# Peltier_1s.net
KiCad netlist of a schematic drawn in Altium Designer
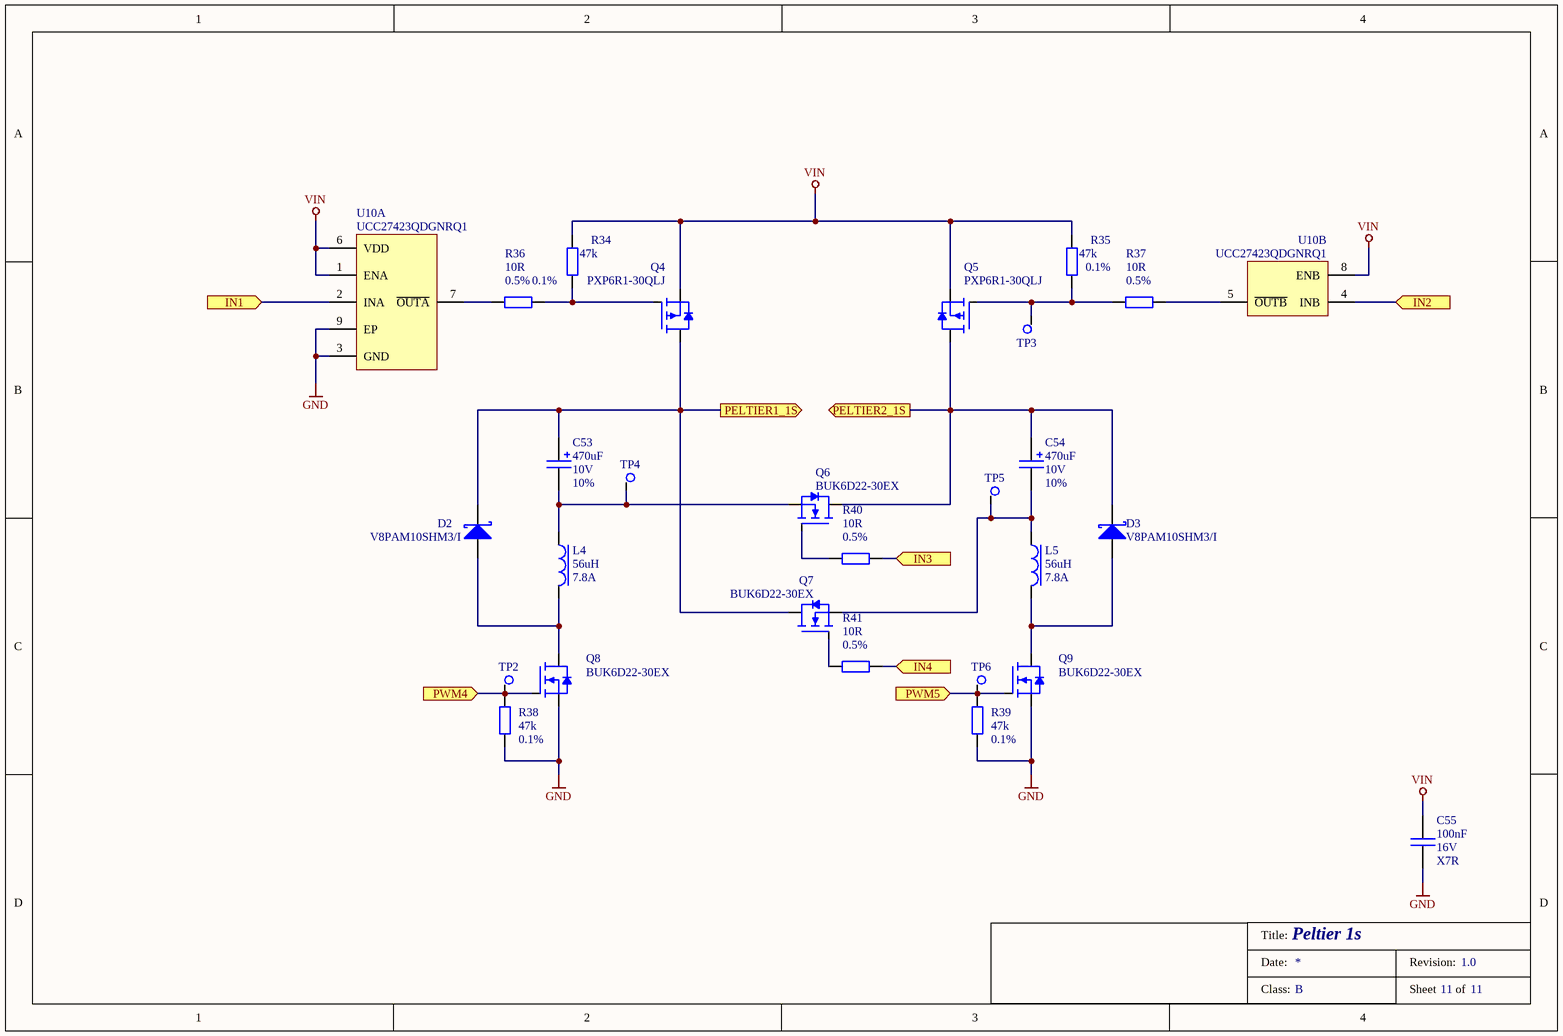
[diagram p0: Peltier_1s.SchDoc]

(export (version "E")
  (design (tool "Eeschema 10.0.6"))
  (components
    (comp (ref "C53")
      (value "470uF")
      (footprint "CT_X")
      (fields
        (field (name "TOLERANCE") "10%")
        (field (name "VOLTAGE") "10V")
        (field (name "PART NUMBER") "CT_470uF_10V_X")
        (field (name "MANUFACTURER") "Kemet")
        (field (name "MANUFACTURER PART NUMBER") "T491X477K010AT")
      )
      (libsource (lib "ProgresjaSpace") (part "C_Pol"))
    )
    (comp (ref "C54")
      (value "470uF")
      (footprint "CT_X")
      (fields
        (field (name "TOLERANCE") "10%")
        (field (name "VOLTAGE") "10V")
        (field (name "PART NUMBER") "CT_470uF_10V_X")
        (field (name "MANUFACTURER") "Kemet")
        (field (name "MANUFACTURER PART NUMBER") "T491X477K010AT")
      )
      (libsource (lib "ProgresjaSpace") (part "C_Pol"))
    )
    (comp (ref "C55")
      (value "100nF")
      (footprint "C_0402")
      (description "Capacitor")
      (fields
        (field (name "VOLTAGE") "16V")
        (field (name "DIELECTRIC") "X7R")
        (field (name "PART NUMBER") "C_100nF_16V_0402")
        (field (name "MANUFACTURER") "Kemet")
      )
      (libsource (lib "ProgresjaSpace") (part "C"))
    )
    (comp (ref "D2")
      (value "V8PAM10SHM3/I")
      (footprint "D_DO_221BC")
      (description "Surface-Mount TMBS (Trench MOS Barrier Schottky) Rectifier")
      (fields (field (name "MANUFACTURER") "Vishay") (field (name "Comment") "D_SHOTTKY"))
      (libsource (lib "ProgresjaSpace") (part "D_SHOTTKY"))
    )
    (comp (ref "D3")
      (value "V8PAM10SHM3/I")
      (footprint "D_DO_221BC")
      (description "Surface-Mount TMBS (Trench MOS Barrier Schottky) Rectifier")
      (fields (field (name "MANUFACTURER") "Vishay") (field (name "Comment") "D_SHOTTKY"))
      (libsource (lib "ProgresjaSpace") (part "D_SHOTTKY"))
    )
    (comp (ref "L4")
      (value "56uH")
      (footprint "L_SRP1770")
      (description "Shielded automotive Inductors, High Temperature")
      (fields
        (field (name "MAX CURRENT") "7.8A")
        (field (name "PART NUMBER") "SRP1770TA-560M")
        (field (name "MANUFACTURER") "Bourns")
      )
      (libsource (lib "ProgresjaSpace") (part "L_Core"))
    )
    (comp (ref "L5")
      (value "56uH")
      (footprint "L_SRP1770")
      (description "Shielded automotive Inductors, High Temperature")
      (fields
        (field (name "MAX CURRENT") "7.8A")
        (field (name "PART NUMBER") "SRP1770TA-560M")
        (field (name "MANUFACTURER") "Bourns")
      )
      (libsource (lib "ProgresjaSpace") (part "L_Core"))
    )
    (comp (ref "Q4")
      (value "PXP6R1-30QLJ")
      (footprint "WDFN_8")
      (description "Low Vgs Single P-Channel")
      (fields (field (name "MANUFACTURER") "NEXPERIA") (field (name "Comment") "Q_PMOSFET"))
      (libsource (lib "ProgresjaSpace") (part "Q_PMOSFET"))
    )
    (comp (ref "Q5")
      (value "PXP6R1-30QLJ")
      (footprint "WDFN_8")
      (description "Low Vgs Single P-Channel")
      (fields (field (name "MANUFACTURER") "NEXPERIA") (field (name "Comment") "Q_PMOSFET"))
      (libsource (lib "ProgresjaSpace") (part "Q_PMOSFET"))
    )
    (comp (ref "Q6")
      (value "BUK6D22-30EX")
      (footprint "SOT_1220")
      (description "Automotive N-Channel 30 V, Low Vgs Treshold")
      (fields (field (name "MANUFACTURER") "NEXPERIA") (field (name "Comment") "Q_NMOSFET"))
      (libsource (lib "ProgresjaSpace") (part "Q_NMOSFET"))
    )
    (comp (ref "Q7")
      (value "BUK6D22-30EX")
      (footprint "SOT_1220")
      (description "Automotive N-Channel 30 V, Low Vgs Treshold")
      (fields (field (name "MANUFACTURER") "NEXPERIA") (field (name "Comment") "Q_NMOSFET"))
      (libsource (lib "ProgresjaSpace") (part "Q_NMOSFET"))
    )
    (comp (ref "Q8")
      (value "BUK6D22-30EX")
      (footprint "SOT_1220")
      (description "Automotive N-Channel 30 V, Low Vgs Treshold")
      (fields (field (name "MANUFACTURER") "NEXPERIA") (field (name "Comment") "Q_NMOSFET"))
      (libsource (lib "ProgresjaSpace") (part "Q_NMOSFET"))
    )
    (comp (ref "Q9")
      (value "BUK6D22-30EX")
      (footprint "SOT_1220")
      (description "Automotive N-Channel 30 V, Low Vgs Treshold")
      (fields (field (name "MANUFACTURER") "NEXPERIA") (field (name "Comment") "Q_NMOSFET"))
      (libsource (lib "ProgresjaSpace") (part "Q_NMOSFET"))
    )
    (comp (ref "R34")
      (value "47k")
      (footprint "R_0402")
      (fields
        (field (name "TOLERANCE") "0.1%")
        (field (name "PART NUMBER") "R_47k_50V_0402")
        (field (name "VOLTAGE") "50V")
        (field (name "MANUFACTURER") "Vishay")
      )
      (libsource (lib "") (part "R_2"))
    )
    (comp (ref "R35")
      (value "47k")
      (footprint "R_0402")
      (fields
        (field (name "TOLERANCE") "0.1%")
        (field (name "PART NUMBER") "R_47k_50V_0402")
        (field (name "VOLTAGE") "50V")
        (field (name "MANUFACTURER") "Vishay")
      )
      (libsource (lib "") (part "R_2"))
    )
    (comp (ref "R36")
      (value "10R")
      (footprint "R_0603")
      (fields
        (field (name "TOLERANCE") "0.5%")
        (field (name "PART NUMBER") "R_10R_75V_0603")
        (field (name "VOLTAGE") "75V")
        (field (name "MANUFACTURER") "Vishay")
      )
      (libsource (lib "ProgresjaSpace") (part "R"))
    )
    (comp (ref "R37")
      (value "10R")
      (footprint "R_0603")
      (fields
        (field (name "TOLERANCE") "0.5%")
        (field (name "PART NUMBER") "R_10R_75V_0603")
        (field (name "VOLTAGE") "75V")
        (field (name "MANUFACTURER") "Vishay")
      )
      (libsource (lib "ProgresjaSpace") (part "R"))
    )
    (comp (ref "R38")
      (value "47k")
      (footprint "R_0402")
      (fields
        (field (name "TOLERANCE") "0.1%")
        (field (name "PART NUMBER") "R_47k_50V_0402")
        (field (name "VOLTAGE") "50V")
        (field (name "MANUFACTURER") "Vishay")
      )
      (libsource (lib "") (part "R_1"))
    )
    (comp (ref "R39")
      (value "47k")
      (footprint "R_0402")
      (fields
        (field (name "TOLERANCE") "0.1%")
        (field (name "PART NUMBER") "R_47k_50V_0402")
        (field (name "VOLTAGE") "50V")
        (field (name "MANUFACTURER") "Vishay")
      )
      (libsource (lib "") (part "R_1"))
    )
    (comp (ref "R40")
      (value "10R")
      (footprint "R_0603")
      (fields
        (field (name "TOLERANCE") "0.5%")
        (field (name "PART NUMBER") "R_10R_75V_0603")
        (field (name "VOLTAGE") "75V")
        (field (name "MANUFACTURER") "Vishay")
      )
      (libsource (lib "ProgresjaSpace") (part "R"))
    )
    (comp (ref "R41")
      (value "10R")
      (footprint "R_0603")
      (fields
        (field (name "TOLERANCE") "0.5%")
        (field (name "PART NUMBER") "R_10R_75V_0603")
        (field (name "VOLTAGE") "75V")
        (field (name "MANUFACTURER") "Vishay")
      )
      (libsource (lib "ProgresjaSpace") (part "R"))
    )
    (comp (ref "TP2")
      (value "TP_TestPoint")
      (footprint "TP_01")
      (fields (field (name "PART NUMBER") "TestPoint1") (field (name "MANUFACTURER") "Progresja Space"))
      (libsource (lib "ProgresjaSpace") (part "TP_TestPoint"))
    )
    (comp (ref "TP3")
      (value "TP_TestPoint")
      (footprint "TP_01")
      (fields (field (name "PART NUMBER") "TestPoint1") (field (name "MANUFACTURER") "Progresja Space"))
      (libsource (lib "ProgresjaSpace") (part "TP_TestPoint"))
    )
    (comp (ref "TP4")
      (value "TP_TestPoint")
      (footprint "TP_01")
      (fields (field (name "PART NUMBER") "TestPoint1") (field (name "MANUFACTURER") "Progresja Space"))
      (libsource (lib "ProgresjaSpace") (part "TP_TestPoint"))
    )
    (comp (ref "TP5")
      (value "TP_TestPoint")
      (footprint "TP_01")
      (fields (field (name "PART NUMBER") "TestPoint1") (field (name "MANUFACTURER") "Progresja Space"))
      (libsource (lib "ProgresjaSpace") (part "TP_TestPoint"))
    )
    (comp (ref "TP6")
      (value "TP_TestPoint")
      (footprint "TP_01")
      (fields (field (name "PART NUMBER") "TestPoint1") (field (name "MANUFACTURER") "Progresja Space"))
      (libsource (lib "ProgresjaSpace") (part "TP_TestPoint"))
    )
    (comp (ref "U10")
      (value "UCC27423QDGNRQ1")
      (footprint "MSOP_8")
      (description "Dual 4-A High-Speed Low-Side MOSFET Drivers With Enable")
      (fields (field (name "PART NUMBER") "UCC27423") (field (name "MANUFACTURER") "TI"))
      (libsource (lib "ProgresjaSpace") (part "IC_UCC27423_Q1"))
    )
  )
  (nets
    (net (code "1") (name "/IN1") (class "Default")
      (node (ref "U10") (pin "2") (pinfunction "INA_2") (pintype "passive"))
    )
    (net (code "2") (name "/IN2") (class "Default")
      (node (ref "U10") (pin "4") (pinfunction "INB_4") (pintype "passive"))
    )
    (net (code "3") (name "/IN3") (class "Default")
      (node (ref "R40") (pin "2") (pinfunction "2_2") (pintype "passive"))
    )
    (net (code "4") (name "/IN4") (class "Default")
      (node (ref "R41") (pin "2") (pinfunction "2_2") (pintype "passive"))
    )
    (net (code "5") (name "/PELTIER1_1S") (class "Default")
      (node (ref "C53") (pin "1") (pinfunction "1_1") (pintype "passive"))
      (node (ref "D2") (pin "2") (pinfunction "K_2") (pintype "passive"))
      (node (ref "Q4") (pin "3") (pinfunction "D_3") (pintype "passive"))
      (node (ref "Q7") (pin "3") (pinfunction "D_3") (pintype "passive"))
    )
    (net (code "6") (name "/PELTIER2_1S") (class "Default")
      (node (ref "C54") (pin "1") (pinfunction "1_1") (pintype "passive"))
      (node (ref "D3") (pin "2") (pinfunction "K_2") (pintype "passive"))
      (node (ref "Q5") (pin "3") (pinfunction "D_3") (pintype "passive"))
      (node (ref "Q6") (pin "3") (pinfunction "D_3") (pintype "passive"))
    )
    (net (code "7") (name "/PWM4") (class "Default")
      (node (ref "Q8") (pin "1") (pinfunction "G_1") (pintype "passive"))
      (node (ref "R38") (pin "1") (pinfunction "1_1") (pintype "passive"))
      (node (ref "TP2") (pin "1") (pinfunction "1_1") (pintype "passive"))
    )
    (net (code "8") (name "/PWM5") (class "Default")
      (node (ref "Q9") (pin "1") (pinfunction "G_1") (pintype "passive"))
      (node (ref "R39") (pin "1") (pinfunction "1_1") (pintype "passive"))
      (node (ref "TP6") (pin "1") (pinfunction "1_1") (pintype "passive"))
    )
    (net (code "9") (name "GND") (class "Default")
      (node (ref "C55") (pin "2") (pinfunction "2_2") (pintype "passive"))
      (node (ref "Q8") (pin "2") (pinfunction "S_2") (pintype "passive"))
      (node (ref "Q9") (pin "2") (pinfunction "S_2") (pintype "passive"))
      (node (ref "R38") (pin "2") (pinfunction "2_2") (pintype "passive"))
      (node (ref "R39") (pin "2") (pinfunction "2_2") (pintype "passive"))
      (node (ref "U10") (pin "3") (pinfunction "GND_3") (pintype "passive"))
      (node (ref "U10") (pin "9") (pinfunction "EP_9") (pintype "passive"))
    )
    (net (code "10") (name "Net-(D2-A)") (class "Default")
      (node (ref "D2") (pin "1") (pinfunction "A_1") (pintype "passive"))
      (node (ref "L4") (pin "2") (pinfunction "2_2") (pintype "passive"))
      (node (ref "Q8") (pin "3") (pinfunction "D_3") (pintype "passive"))
    )
    (net (code "11") (name "Net-(D3-A)") (class "Default")
      (node (ref "D3") (pin "1") (pinfunction "A_1") (pintype "passive"))
      (node (ref "L5") (pin "2") (pinfunction "2_2") (pintype "passive"))
      (node (ref "Q9") (pin "3") (pinfunction "D_3") (pintype "passive"))
    )
    (net (code "12") (name "Net-(Q4-G)") (class "Default")
      (node (ref "Q4") (pin "1") (pinfunction "G_1") (pintype "passive"))
      (node (ref "R34") (pin "2") (pinfunction "2_2") (pintype "passive"))
      (node (ref "R36") (pin "2") (pinfunction "2_2") (pintype "passive"))
    )
    (net (code "13") (name "Net-(Q5-G)") (class "Default")
      (node (ref "Q5") (pin "1") (pinfunction "G_1") (pintype "passive"))
      (node (ref "R35") (pin "2") (pinfunction "2_2") (pintype "passive"))
      (node (ref "R37") (pin "1") (pinfunction "1_1") (pintype "passive"))
      (node (ref "TP3") (pin "1") (pinfunction "1_1") (pintype "passive"))
    )
    (net (code "14") (name "Net-(Q6-G)") (class "Default")
      (node (ref "Q6") (pin "1") (pinfunction "G_1") (pintype "passive"))
      (node (ref "R40") (pin "1") (pinfunction "1_1") (pintype "passive"))
    )
    (net (code "15") (name "Net-(Q6-S)") (class "Default")
      (node (ref "C53") (pin "2") (pinfunction "2_2") (pintype "passive"))
      (node (ref "L4") (pin "1") (pinfunction "1_1") (pintype "passive"))
      (node (ref "Q6") (pin "2") (pinfunction "S_2") (pintype "passive"))
      (node (ref "TP4") (pin "1") (pinfunction "1_1") (pintype "passive"))
    )
    (net (code "16") (name "Net-(Q7-G)") (class "Default")
      (node (ref "Q7") (pin "1") (pinfunction "G_1") (pintype "passive"))
      (node (ref "R41") (pin "1") (pinfunction "1_1") (pintype "passive"))
    )
    (net (code "17") (name "Net-(Q7-S)") (class "Default")
      (node (ref "C54") (pin "2") (pinfunction "2_2") (pintype "passive"))
      (node (ref "L5") (pin "1") (pinfunction "1_1") (pintype "passive"))
      (node (ref "Q7") (pin "2") (pinfunction "S_2") (pintype "passive"))
      (node (ref "TP5") (pin "1") (pinfunction "1_1") (pintype "passive"))
    )
    (net (code "18") (name "Net-(U10A-~{OUTA})") (class "Default")
      (node (ref "R36") (pin "1") (pinfunction "1_1") (pintype "passive"))
      (node (ref "U10") (pin "7") (pinfunction "~{OUTA}_7") (pintype "passive"))
    )
    (net (code "19") (name "Net-(U10B-~{OUTB})") (class "Default")
      (node (ref "R37") (pin "2") (pinfunction "2_2") (pintype "passive"))
      (node (ref "U10") (pin "5") (pinfunction "~{OUTB}_5") (pintype "passive"))
    )
    (net (code "20") (name "VIN") (class "Default")
      (node (ref "C55") (pin "1") (pinfunction "1_1") (pintype "passive"))
      (node (ref "Q4") (pin "2") (pinfunction "S_2") (pintype "passive"))
      (node (ref "Q5") (pin "2") (pinfunction "S_2") (pintype "passive"))
      (node (ref "R34") (pin "1") (pinfunction "1_1") (pintype "passive"))
      (node (ref "R35") (pin "1") (pinfunction "1_1") (pintype "passive"))
      (node (ref "U10") (pin "1") (pinfunction "ENA_1") (pintype "passive"))
      (node (ref "U10") (pin "6") (pinfunction "VDD_6") (pintype "passive"))
      (node (ref "U10") (pin "8") (pinfunction "ENB_8") (pintype "passive"))
    )
  )
)
